# Voltage_Measurement.net
KiCad netlist of a schematic drawn in Altium Designer
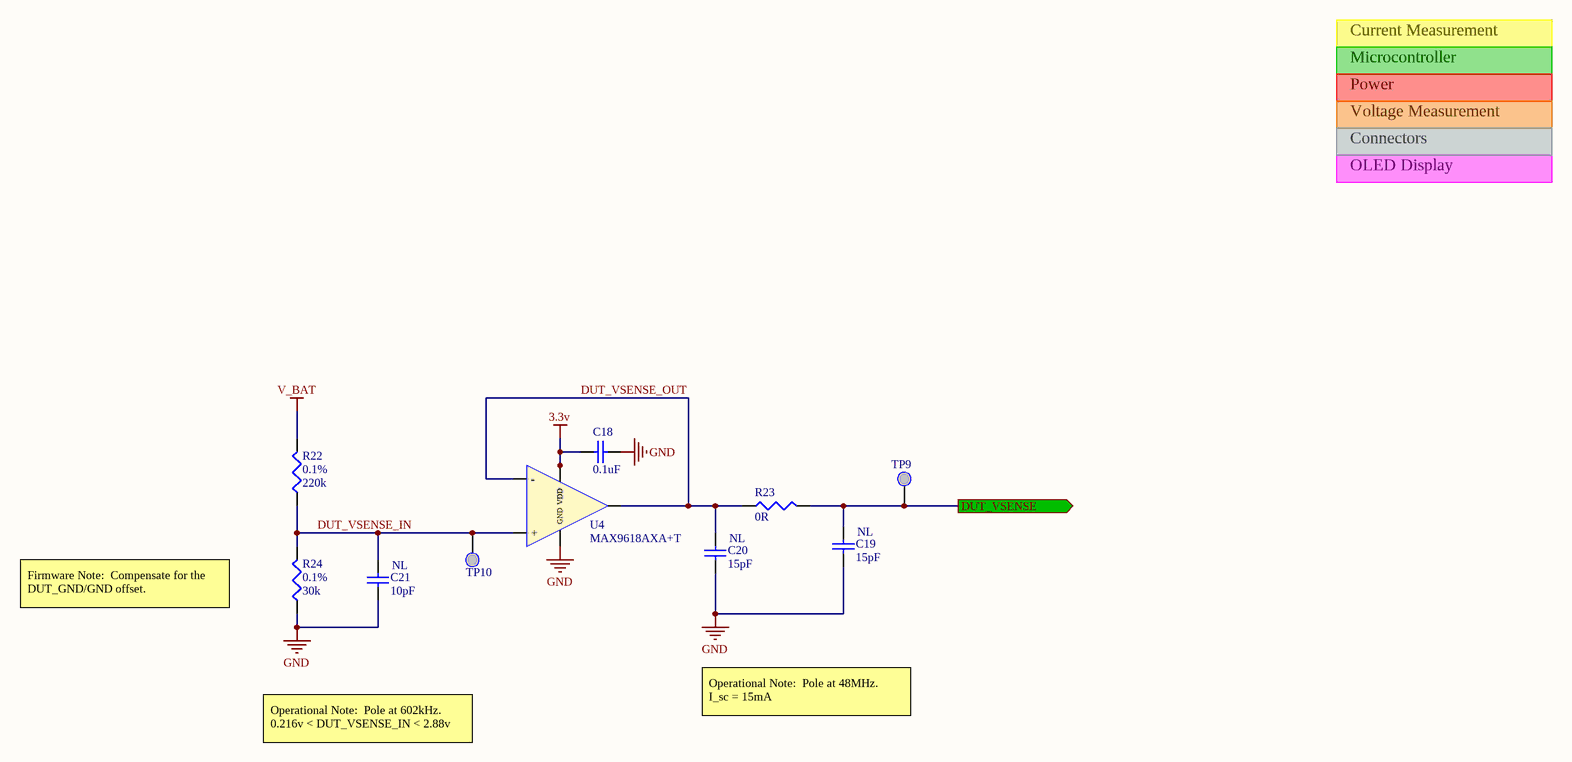
[diagram p0: Voltage Measurement.SchDoc]

(export (version "E")
  (design (tool "Eeschema 10.0.6"))
  (components
    (comp (ref "C18")
      (value "0.1uF")
      (footprint "CAP0402R")
      (fields (field (name "TOLERANCE") "20%") (field (name "MFG") "Vishay") (field (name "VOLTAGE") "10v"))
      (libsource (lib "Altium Library") (part "0.1uF (0402)"))
    )
    (comp (ref "C19")
      (value "15pF")
      (footprint "CAP0402R")
      (fields
        (field (name "TOLERANCE") "5%")
        (field (name "MFG") "Vishay")
        (field (name "VOLTAGE") "50v")
        (field (name "LOAD") "NL")
      )
      (libsource (lib "Altium Library") (part "15pF (0402)"))
    )
    (comp (ref "C20")
      (value "15pF")
      (footprint "CAP0402R")
      (fields
        (field (name "TOLERANCE") "5%")
        (field (name "MFG") "Vishay")
        (field (name "VOLTAGE") "50v")
        (field (name "LOAD") "NL")
      )
      (libsource (lib "Altium Library") (part "15pF (0402)"))
    )
    (comp (ref "C21")
      (value "10pF")
      (footprint "CAP0402R")
      (fields
        (field (name "TOLERANCE") "5%")
        (field (name "MFG") "Vishay")
        (field (name "VOLTAGE") "50v")
        (field (name "LOAD") "NL")
      )
      (libsource (lib "Altium Library") (part "10pF (0402)"))
    )
    (comp (ref "R22")
      (value "220k")
      (footprint "RES0603R")
      (fields (field (name "POWER") "0.1W") (field (name "TOLERANCE") "0.1%"))
      (libsource (lib "Altium Library") (part "220k 0.1% (0603)"))
    )
    (comp (ref "R23")
      (value "0R")
      (footprint "RES0402R")
      (fields (field (name "MFG") "Vishay"))
      (libsource (lib "Altium Library_EE4951") (part "0R (0402)"))
    )
    (comp (ref "R24")
      (value "30k")
      (footprint "RES0603R")
      (fields (field (name "POWER") "0.1W") (field (name "TOLERANCE") "0.1%"))
      (libsource (lib "Altium Library") (part "30k 0.1% (0603)"))
    )
    (comp (ref "TP9")
      (value "NONE")
      (footprint "TESTPOINT - 1.5mm Round Pad")
      (description "1.5mm Testpoint")
      (libsource (lib "Altium Library_EE4951") (part "Testpoint 1.5mm SMD"))
    )
    (comp (ref "TP10")
      (value "NONE")
      (footprint "TESTPOINT - 1.5mm Round Pad")
      (description "1.5mm Testpoint")
      (libsource (lib "Altium Library_EE4951") (part "Testpoint 1.5mm SMD"))
    )
    (comp (ref "U4")
      (value "MAX9618AXA+T")
      (footprint "SC70")
      (description "Op Amp - 1 Channel Zero Drift")
      (fields (field (name "MFG") "MAXIM"))
      (libsource (lib "Altium Library") (part "MAX9618AXA"))
    )
  )
  (nets
    (net (code "1") (name "/DUT_VSENSE") (class "Default")
      (node (ref "C19") (pin "1") (pinfunction "1_1") (pintype "passive"))
      (node (ref "R23") (pin "2") (pinfunction "2_2") (pintype "passive"))
      (node (ref "TP9") (pin "1") (pinfunction "1_1") (pintype "passive"))
    )
    (net (code "2") (name "/DUT_VSENSE_IN") (class "Default")
      (node (ref "C21") (pin "1") (pinfunction "1_1") (pintype "passive"))
      (node (ref "R22") (pin "1") (pinfunction "1_1") (pintype "passive"))
      (node (ref "R24") (pin "2") (pinfunction "2_2") (pintype "passive"))
      (node (ref "TP10") (pin "1") (pinfunction "1_1") (pintype "passive"))
      (node (ref "U4") (pin "1") (pinfunction "+_1") (pintype "passive"))
    )
    (net (code "3") (name "/DUT_VSENSE_OUT") (class "Default")
      (node (ref "C20") (pin "1") (pinfunction "1_1") (pintype "passive"))
      (node (ref "R23") (pin "1") (pinfunction "1_1") (pintype "passive"))
      (node (ref "U4") (pin "3") (pinfunction "-_3") (pintype "passive"))
      (node (ref "U4") (pin "4") (pinfunction "OUT_4") (pintype "passive"))
    )
    (net (code "4") (name "3.3v") (class "Default")
      (node (ref "C18") (pin "1") (pinfunction "1_1") (pintype "passive"))
      (node (ref "U4") (pin "5") (pinfunction "VDD_5") (pintype "passive"))
      (node (ref "U4") (pin "6") (pinfunction "VDD_6") (pintype "passive"))
    )
    (net (code "5") (name "GND") (class "Default")
      (node (ref "C18") (pin "2") (pinfunction "2_2") (pintype "passive"))
      (node (ref "C19") (pin "2") (pinfunction "2_2") (pintype "passive"))
      (node (ref "C20") (pin "2") (pinfunction "2_2") (pintype "passive"))
      (node (ref "C21") (pin "2") (pinfunction "2_2") (pintype "passive"))
      (node (ref "R24") (pin "1") (pinfunction "1_1") (pintype "passive"))
      (node (ref "U4") (pin "2") (pinfunction "GND_2") (pintype "passive"))
    )
    (net (code "6") (name "V_BAT") (class "Default")
      (node (ref "R22") (pin "2") (pinfunction "2_2") (pintype "passive"))
    )
  )
)
